# AD9834.net
KiCad netlist of a schematic drawn in Altium Designer
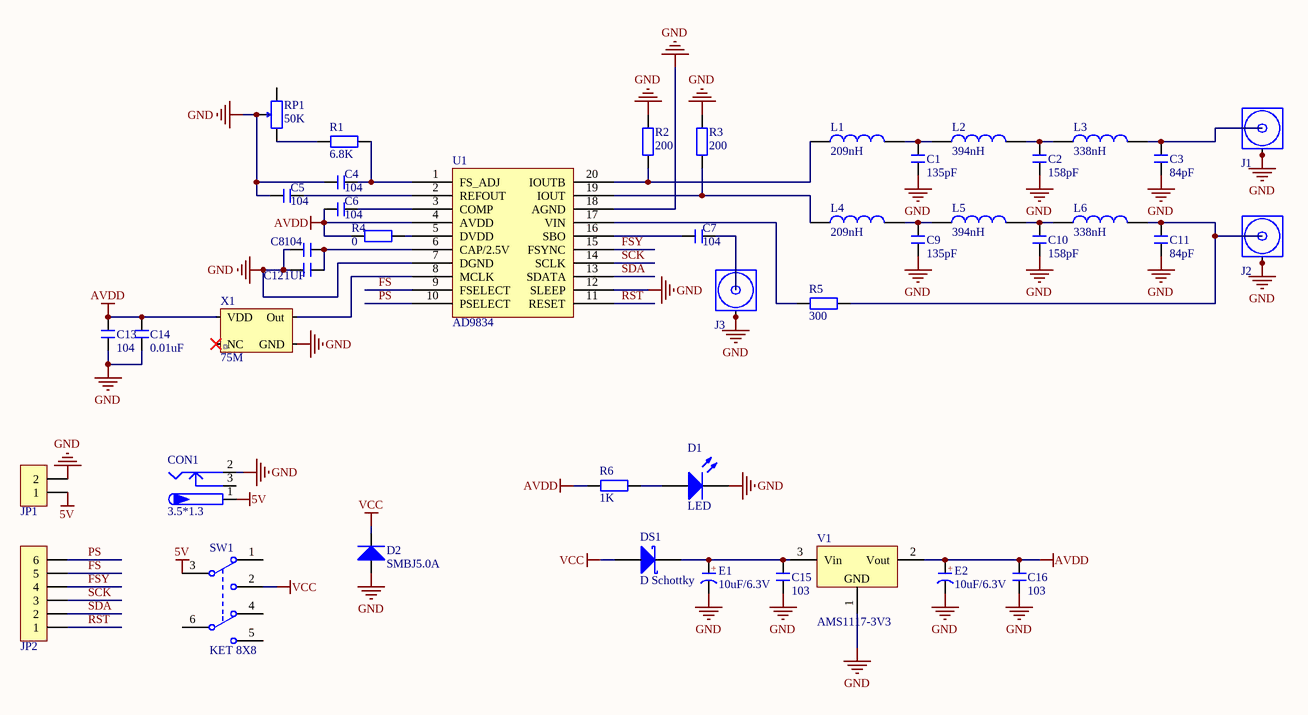
[diagram p0: AD9834.SchDoc]

(export (version "E")
  (design (tool "Eeschema 10.0.6"))
  (components
    (comp (ref "C1")
      (value "135pF")
      (footprint "C 0603")
      (description "无极性贴片电容")
      (fields (field (name "版权归属") "源创客"))
      (libsource (lib "电阻-电容-电感") (part "C"))
    )
    (comp (ref "C2")
      (value "158pF")
      (footprint "C 0603")
      (description "无极性贴片电容")
      (fields (field (name "版权归属") "源创客"))
      (libsource (lib "电阻-电容-电感") (part "C"))
    )
    (comp (ref "C3")
      (value "84pF")
      (footprint "C 0603")
      (description "无极性贴片电容")
      (fields (field (name "版权归属") "源创客"))
      (libsource (lib "电阻-电容-电感") (part "C"))
    )
    (comp (ref "C4")
      (value "104")
      (footprint "C 0805")
      (description "无极性贴片电容")
      (fields (field (name "版权归属") "源创客"))
      (libsource (lib "电阻-电容-电感") (part "C"))
    )
    (comp (ref "C5")
      (value "104")
      (footprint "C 0805")
      (description "无极性贴片电容")
      (fields (field (name "版权归属") "源创客"))
      (libsource (lib "电阻-电容-电感") (part "C"))
    )
    (comp (ref "C6")
      (value "104")
      (footprint "C 0805")
      (description "无极性贴片电容")
      (fields (field (name "版权归属") "源创客"))
      (libsource (lib "电阻-电容-电感") (part "C"))
    )
    (comp (ref "C7")
      (value "104")
      (footprint "C 0805")
      (description "无极性贴片电容")
      (fields (field (name "版权归属") "源创客"))
      (libsource (lib "电阻-电容-电感") (part "C"))
    )
    (comp (ref "C8")
      (value "104")
      (footprint "C 0805")
      (description "无极性贴片电容")
      (fields (field (name "版权归属") "源创客"))
      (libsource (lib "电阻-电容-电感") (part "C"))
    )
    (comp (ref "C9")
      (value "135pF")
      (footprint "C 0603")
      (description "无极性贴片电容")
      (fields (field (name "版权归属") "源创客"))
      (libsource (lib "电阻-电容-电感") (part "C"))
    )
    (comp (ref "C10")
      (value "158pF")
      (footprint "C 0603")
      (description "无极性贴片电容")
      (fields (field (name "版权归属") "源创客"))
      (libsource (lib "电阻-电容-电感") (part "C"))
    )
    (comp (ref "C11")
      (value "84pF")
      (footprint "C 0603")
      (description "无极性贴片电容")
      (fields (field (name "版权归属") "源创客"))
      (libsource (lib "电阻-电容-电感") (part "C"))
    )
    (comp (ref "C12")
      (value "1UF")
      (footprint "C 0805")
      (description "无极性贴片电容")
      (fields (field (name "版权归属") "源创客"))
      (libsource (lib "电阻-电容-电感") (part "C"))
    )
    (comp (ref "C13")
      (value "104")
      (footprint "C 0805")
      (description "无极性贴片电容")
      (fields (field (name "版权归属") "源创客"))
      (libsource (lib "电阻-电容-电感") (part "C"))
    )
    (comp (ref "C14")
      (value "0.01uF")
      (footprint "C 0805")
      (description "无极性贴片电容")
      (fields (field (name "版权归属") "源创客"))
      (libsource (lib "电阻-电容-电感") (part "C"))
    )
    (comp (ref "C15")
      (value "103")
      (footprint "C 0805")
      (description "无极性贴片电容")
      (fields (field (name "版权归属") "源创客"))
      (libsource (lib "电阻-电容-电感") (part "C"))
    )
    (comp (ref "C16")
      (value "103")
      (footprint "C 0805")
      (description "无极性贴片电容")
      (fields (field (name "版权归属") "源创客"))
      (libsource (lib "电阻-电容-电感") (part "C"))
    )
    (comp (ref "CON1")
      (value "3.5*1.3")
      (footprint "DC-005")
      (description "低压电源接口")
      (fields (field (name "版权归属") "源创客"))
      (libsource (lib "接口类") (part "P-DC"))
    )
    (comp (ref "D1")
      (value "LED")
      (footprint "LED_0805")
      (description "发光二极管")
      (fields (field (name "PUBLISHER") "Altium Limited"))
      (libsource (lib "LIB") (part "LED"))
    )
    (comp (ref "D2")
      (value "TVS")
      (footprint "DIODE-SMB")
      (description "TVS保护")
      (fields (field (name "TYPE") "SMBJ5.0A") (field (name "PUBLISHER") "Altium Limited"))
      (libsource (lib "LIB") (part "TVS"))
    )
    (comp (ref "DS1")
      (value "D Schottky")
      (footprint "SMB")
      (description "Schottky Diode")
      (fields (field (name "PUBLISHER") "Altium Limited"))
      (libsource (lib "LIB") (part "D Schottky"))
    )
    (comp (ref "E1")
      (value "10uF/6.3V")
      (footprint "CD B(3528)")
      (description "贴片钽电容")
      (fields (field (name "版权归属") "源创客"))
      (libsource (lib "电阻-电容-电感") (part "C-CD"))
    )
    (comp (ref "E2")
      (value "10uF/6.3V")
      (footprint "CD B(3528)")
      (description "贴片钽电容")
      (fields (field (name "版权归属") "源创客"))
      (libsource (lib "电阻-电容-电感") (part "C-CD"))
    )
    (comp (ref "J1") (value "COAX") (footprint "MCX5.08-5-H") (libsource (lib "LIB") (part "COAX")))
    (comp (ref "J2") (value "COAX") (footprint "MCX5.08-5-H") (libsource (lib "LIB") (part "COAX")))
    (comp (ref "J3") (value "COAX") (footprint "MCX5.08-5-H") (libsource (lib "LIB") (part "COAX")))
    (comp (ref "JP1")
      (value "HDR-1X2")
      (footprint "XH2.54-2P_H")
      (description "2P接插件")
      (fields (field (name "版权归属") "源创客"))
      (libsource (lib "接插件") (part "Header 2"))
    )
    (comp (ref "JP2")
      (value "HDR-1X6")
      (footprint "HDR-1X6")
      (description "6P接插件")
      (fields (field (name "版权归属") "源创客"))
      (libsource (lib "接插件") (part "Header 6"))
    )
    (comp (ref "L1")
      (value "209nH")
      (footprint "L 0603")
      (description "小功率贴片电感")
      (fields (field (name "版权归属") "源创客"))
      (libsource (lib "电阻-电容-电感") (part "L"))
    )
    (comp (ref "L2")
      (value "394nH")
      (footprint "L 0603")
      (description "小功率贴片电感")
      (fields (field (name "版权归属") "源创客"))
      (libsource (lib "电阻-电容-电感") (part "L"))
    )
    (comp (ref "L3")
      (value "338nH")
      (footprint "L 0603")
      (description "小功率贴片电感")
      (fields (field (name "版权归属") "源创客"))
      (libsource (lib "电阻-电容-电感") (part "L"))
    )
    (comp (ref "L4")
      (value "209nH")
      (footprint "L 0603")
      (description "小功率贴片电感")
      (fields (field (name "版权归属") "源创客"))
      (libsource (lib "电阻-电容-电感") (part "L"))
    )
    (comp (ref "L5")
      (value "394nH")
      (footprint "L 0603")
      (description "小功率贴片电感")
      (fields (field (name "版权归属") "源创客"))
      (libsource (lib "电阻-电容-电感") (part "L"))
    )
    (comp (ref "L6")
      (value "338nH")
      (footprint "L 0603")
      (description "小功率贴片电感")
      (fields (field (name "版权归属") "源创客"))
      (libsource (lib "电阻-电容-电感") (part "L"))
    )
    (comp (ref "R1")
      (value "6.8K")
      (footprint "R 0603")
      (description "贴片电阻")
      (fields (field (name "版权归属") "源创客"))
      (libsource (lib "电阻-电容-电感") (part "R"))
    )
    (comp (ref "R2")
      (value "200")
      (footprint "R 0603")
      (description "贴片电阻")
      (fields (field (name "版权归属") "源创客"))
      (libsource (lib "电阻-电容-电感") (part "R"))
    )
    (comp (ref "R3")
      (value "200")
      (footprint "R 0603")
      (description "贴片电阻")
      (fields (field (name "版权归属") "源创客"))
      (libsource (lib "电阻-电容-电感") (part "R"))
    )
    (comp (ref "R4")
      (value "0")
      (footprint "R 0603")
      (description "贴片电阻")
      (fields (field (name "版权归属") "源创客"))
      (libsource (lib "电阻-电容-电感") (part "R"))
    )
    (comp (ref "R5")
      (value "300")
      (footprint "R 0603")
      (description "贴片电阻")
      (fields (field (name "版权归属") "源创客"))
      (libsource (lib "电阻-电容-电感") (part "R"))
    )
    (comp (ref "R6")
      (value "1K")
      (footprint "R 0805")
      (description "贴片电阻")
      (fields (field (name "版权归属") "源创客"))
      (libsource (lib "电阻-电容-电感") (part "R"))
    )
    (comp (ref "RP1")
      (value "50K")
      (footprint "3296W")
      (description "插件单联电位器")
      (fields (field (name "版权归属") "源创客"))
      (libsource (lib "电阻-电容-电感") (part "RP-ID"))
    )
    (comp (ref "SW1")
      (value "KET 8X8")
      (footprint "KFT DIP-8X8")
      (description "8*8自锁开关")
      (fields (field (name "版权归属") "源创客"))
      (libsource (lib "按键-开关") (part "KET 8X8"))
    )
    (comp (ref "U1")
      (value "AD9834")
      (footprint "TSSOP20_N")
      (description "20mW Power,2,3V to 5.5V,75MHz, Complete DDS")
      (libsource (lib "LIB") (part "AD9834"))
    )
    (comp (ref "V1")
      (value "AMS1117-3V3")
      (footprint "SOT223_N")
      (description "三端稳压芯片")
      (fields (field (name "版权归属") "源创客"))
      (libsource (lib "IC芯片") (part "AMS1117"))
    )
    (comp (ref "X1")
      (value "75M")
      (footprint "X-CPX75")
      (description "有源晶振")
      (fields (field (name "FREQUENCY") "75M"))
      (libsource (lib "LIB") (part "XTAL_Oscillator"))
    )
  )
  (nets
    (net (code "1") (name "/FS") (class "Default")
      (node (ref "JP2") (pin "5") (pinfunction "5_5") (pintype "passive"))
      (node (ref "U1") (pin "9") (pinfunction "FSELECT_9") (pintype "passive"))
    )
    (net (code "2") (name "/FSY") (class "Default")
      (node (ref "JP2") (pin "4") (pinfunction "4_4") (pintype "passive"))
      (node (ref "U1") (pin "15") (pinfunction "FSYNC_15") (pintype "passive"))
    )
    (net (code "3") (name "/PS") (class "Default")
      (node (ref "JP2") (pin "6") (pinfunction "6_6") (pintype "passive"))
      (node (ref "U1") (pin "10") (pinfunction "PSELECT_10") (pintype "passive"))
    )
    (net (code "4") (name "/RST") (class "Default")
      (node (ref "JP2") (pin "1") (pinfunction "1_1") (pintype "passive"))
      (node (ref "U1") (pin "11") (pinfunction "RESET_11") (pintype "passive"))
    )
    (net (code "5") (name "/SCK") (class "Default")
      (node (ref "JP2") (pin "3") (pinfunction "3_3") (pintype "passive"))
      (node (ref "U1") (pin "14") (pinfunction "SCLK_14") (pintype "passive"))
    )
    (net (code "6") (name "/SDA") (class "Default")
      (node (ref "JP2") (pin "2") (pinfunction "2_2") (pintype "passive"))
      (node (ref "U1") (pin "13") (pinfunction "SDATA_13") (pintype "passive"))
    )
    (net (code "7") (name "5V") (class "Default")
      (node (ref "CON1") (pin "1") (pintype "power_in"))
      (node (ref "JP1") (pin "1") (pinfunction "1_1") (pintype "passive"))
      (node (ref "SW1") (pin "3") (pinfunction "NO1_3") (pintype "passive"))
    )
    (net (code "8") (name "AVDD") (class "Default")
      (node (ref "C13") (pin "2") (pinfunction "2_2") (pintype "passive"))
      (node (ref "C14") (pin "2") (pinfunction "2_2") (pintype "passive"))
      (node (ref "C16") (pin "2") (pinfunction "2_2") (pintype "passive"))
      (node (ref "C6") (pin "1") (pinfunction "1_1") (pintype "passive"))
      (node (ref "E2") (pin "1") (pinfunction "A_1") (pintype "passive"))
      (node (ref "R4") (pin "1") (pinfunction "1_1") (pintype "passive"))
      (node (ref "R6") (pin "1") (pinfunction "1_1") (pintype "passive"))
      (node (ref "U1") (pin "4") (pinfunction "AVDD_4") (pintype "passive"))
      (node (ref "V1") (pin "2") (pinfunction "Vout_2") (pintype "passive"))
      (node (ref "X1") (pin "4") (pinfunction "VDD_4") (pintype "passive"))
    )
    (net (code "9") (name "GND") (class "Default")
      (node (ref "C1") (pin "1") (pinfunction "1_1") (pintype "passive"))
      (node (ref "C10") (pin "1") (pinfunction "1_1") (pintype "passive"))
      (node (ref "C11") (pin "1") (pinfunction "1_1") (pintype "passive"))
      (node (ref "C12") (pin "1") (pinfunction "1_1") (pintype "passive"))
      (node (ref "C13") (pin "1") (pinfunction "1_1") (pintype "passive"))
      (node (ref "C14") (pin "1") (pinfunction "1_1") (pintype "passive"))
      (node (ref "C15") (pin "1") (pinfunction "1_1") (pintype "passive"))
      (node (ref "C16") (pin "1") (pinfunction "1_1") (pintype "passive"))
      (node (ref "C2") (pin "1") (pinfunction "1_1") (pintype "passive"))
      (node (ref "C3") (pin "1") (pinfunction "1_1") (pintype "passive"))
      (node (ref "C4") (pin "1") (pinfunction "1_1") (pintype "passive"))
      (node (ref "C5") (pin "1") (pinfunction "1_1") (pintype "passive"))
      (node (ref "C8") (pin "1") (pinfunction "1_1") (pintype "passive"))
      (node (ref "C9") (pin "1") (pinfunction "1_1") (pintype "passive"))
      (node (ref "CON1") (pin "2") (pintype "power_in"))
      (node (ref "D1") (pin "2") (pinfunction "K_2") (pintype "passive"))
      (node (ref "D2") (pin "1") (pinfunction "A_1") (pintype "passive"))
      (node (ref "E1") (pin "2") (pinfunction "K_2") (pintype "passive"))
      (node (ref "E2") (pin "2") (pinfunction "K_2") (pintype "passive"))
      (node (ref "J1") (pin "2") (pinfunction "GND_2") (pintype "passive"))
      (node (ref "J1") (pin "3") (pinfunction "GND_3") (pintype "passive"))
      (node (ref "J1") (pin "4") (pinfunction "GND_4") (pintype "passive"))
      (node (ref "J1") (pin "5") (pinfunction "GND_5") (pintype "passive"))
      (node (ref "J2") (pin "2") (pinfunction "GND_2") (pintype "passive"))
      (node (ref "J2") (pin "3") (pinfunction "GND_3") (pintype "passive"))
      (node (ref "J2") (pin "4") (pinfunction "GND_4") (pintype "passive"))
      (node (ref "J2") (pin "5") (pinfunction "GND_5") (pintype "passive"))
      (node (ref "J3") (pin "2") (pinfunction "GND_2") (pintype "passive"))
      (node (ref "J3") (pin "3") (pinfunction "GND_3") (pintype "passive"))
      (node (ref "J3") (pin "4") (pinfunction "GND_4") (pintype "passive"))
      (node (ref "J3") (pin "5") (pinfunction "GND_5") (pintype "passive"))
      (node (ref "JP1") (pin "2") (pinfunction "2_2") (pintype "passive"))
      (node (ref "R2") (pin "1") (pinfunction "1_1") (pintype "passive"))
      (node (ref "R3") (pin "1") (pinfunction "1_1") (pintype "passive"))
      (node (ref "RP1") (pin "2") (pinfunction "2_2") (pintype "passive"))
      (node (ref "U1") (pin "12") (pinfunction "SLEEP_12") (pintype "passive"))
      (node (ref "U1") (pin "18") (pinfunction "AGND_18") (pintype "passive"))
      (node (ref "U1") (pin "7") (pinfunction "DGND_7") (pintype "passive"))
      (node (ref "V1") (pin "1") (pinfunction "GND_1") (pintype "passive"))
      (node (ref "X1") (pin "2") (pinfunction "GND_2") (pintype "passive"))
    )
    (net (code "10") (name "Net-(C1-Pad2)") (class "Default")
      (node (ref "C1") (pin "2") (pinfunction "2_2") (pintype "passive"))
      (node (ref "L1") (pin "2") (pinfunction "2_2") (pintype "passive"))
      (node (ref "L2") (pin "1") (pinfunction "1_1") (pintype "passive"))
    )
    (net (code "11") (name "Net-(C2-Pad2)") (class "Default")
      (node (ref "C2") (pin "2") (pinfunction "2_2") (pintype "passive"))
      (node (ref "L2") (pin "2") (pinfunction "2_2") (pintype "passive"))
      (node (ref "L3") (pin "1") (pinfunction "1_1") (pintype "passive"))
    )
    (net (code "12") (name "Net-(C9-Pad2)") (class "Default")
      (node (ref "C9") (pin "2") (pinfunction "2_2") (pintype "passive"))
      (node (ref "L4") (pin "2") (pinfunction "2_2") (pintype "passive"))
      (node (ref "L5") (pin "1") (pinfunction "1_1") (pintype "passive"))
    )
    (net (code "13") (name "Net-(C10-Pad2)") (class "Default")
      (node (ref "C10") (pin "2") (pinfunction "2_2") (pintype "passive"))
      (node (ref "L5") (pin "2") (pinfunction "2_2") (pintype "passive"))
      (node (ref "L6") (pin "1") (pinfunction "1_1") (pintype "passive"))
    )
    (net (code "14") (name "Net-(D1-A)") (class "Default")
      (node (ref "D1") (pin "1") (pinfunction "A_1") (pintype "passive"))
      (node (ref "R6") (pin "2") (pinfunction "2_2") (pintype "passive"))
    )
    (net (code "15") (name "Net-(E1-A)") (class "Default")
      (node (ref "C15") (pin "2") (pinfunction "2_2") (pintype "passive"))
      (node (ref "DS1") (pin "2") (pinfunction "2_2") (pintype "passive"))
      (node (ref "E1") (pin "1") (pinfunction "A_1") (pintype "passive"))
      (node (ref "V1") (pin "3") (pinfunction "Vin_3") (pintype "passive"))
    )
    (net (code "16") (name "Net-(J1-Signal)") (class "Default")
      (node (ref "C3") (pin "2") (pinfunction "2_2") (pintype "passive"))
      (node (ref "J1") (pin "1") (pinfunction "Signal_1") (pintype "passive"))
      (node (ref "L3") (pin "2") (pinfunction "2_2") (pintype "passive"))
    )
    (net (code "17") (name "Net-(J2-Signal)") (class "Default")
      (node (ref "C11") (pin "2") (pinfunction "2_2") (pintype "passive"))
      (node (ref "J2") (pin "1") (pinfunction "Signal_1") (pintype "passive"))
      (node (ref "L6") (pin "2") (pinfunction "2_2") (pintype "passive"))
      (node (ref "R5") (pin "2") (pinfunction "2_2") (pintype "passive"))
    )
    (net (code "18") (name "Net-(J3-Signal)") (class "Default")
      (node (ref "C7") (pin "2") (pinfunction "2_2") (pintype "passive"))
      (node (ref "J3") (pin "1") (pinfunction "Signal_1") (pintype "passive"))
    )
    (net (code "19") (name "Net-(R1-Pad1)") (class "Default")
      (node (ref "R1") (pin "1") (pinfunction "1_1") (pintype "passive"))
      (node (ref "RP1") (pin "1") (pinfunction "1_1") (pintype "passive"))
    )
    (net (code "20") (name "Net-(U1-CAP{slash}2.5V)") (class "Default")
      (node (ref "C12") (pin "2") (pinfunction "2_2") (pintype "passive"))
      (node (ref "C8") (pin "2") (pinfunction "2_2") (pintype "passive"))
      (node (ref "U1") (pin "6") (pinfunction "CAP/2.5V_6") (pintype "passive"))
    )
    (net (code "21") (name "Net-(U1-COMP)") (class "Default")
      (node (ref "C6") (pin "2") (pinfunction "2_2") (pintype "passive"))
      (node (ref "U1") (pin "3") (pinfunction "COMP_3") (pintype "passive"))
    )
    (net (code "22") (name "Net-(U1-DVDD)") (class "Default")
      (node (ref "R4") (pin "2") (pinfunction "2_2") (pintype "passive"))
      (node (ref "U1") (pin "5") (pinfunction "DVDD_5") (pintype "passive"))
    )
    (net (code "23") (name "Net-(U1-FS_ADJ)") (class "Default")
      (node (ref "C4") (pin "2") (pinfunction "2_2") (pintype "passive"))
      (node (ref "R1") (pin "2") (pinfunction "2_2") (pintype "passive"))
      (node (ref "U1") (pin "1") (pinfunction "FS_ADJ_1") (pintype "passive"))
    )
    (net (code "24") (name "Net-(U1-IOUT)") (class "Default")
      (node (ref "L4") (pin "1") (pinfunction "1_1") (pintype "passive"))
      (node (ref "R3") (pin "2") (pinfunction "2_2") (pintype "passive"))
      (node (ref "U1") (pin "19") (pinfunction "IOUT_19") (pintype "passive"))
    )
    (net (code "25") (name "Net-(U1-IOUTB)") (class "Default")
      (node (ref "L1") (pin "1") (pinfunction "1_1") (pintype "passive"))
      (node (ref "R2") (pin "2") (pinfunction "2_2") (pintype "passive"))
      (node (ref "U1") (pin "20") (pinfunction "IOUTB_20") (pintype "passive"))
    )
    (net (code "26") (name "Net-(U1-MCLK)") (class "Default")
      (node (ref "U1") (pin "8") (pinfunction "MCLK_8") (pintype "passive"))
      (node (ref "X1") (pin "3") (pinfunction "Out_3") (pintype "passive"))
    )
    (net (code "27") (name "Net-(U1-REFOUT)") (class "Default")
      (node (ref "C5") (pin "2") (pinfunction "2_2") (pintype "passive"))
      (node (ref "U1") (pin "2") (pinfunction "REFOUT_2") (pintype "passive"))
    )
    (net (code "28") (name "Net-(U1-SBO)") (class "Default")
      (node (ref "C7") (pin "1") (pinfunction "1_1") (pintype "passive"))
      (node (ref "U1") (pin "16") (pinfunction "SBO_16") (pintype "passive"))
    )
    (net (code "29") (name "Net-(U1-VIN)") (class "Default")
      (node (ref "R5") (pin "1") (pinfunction "1_1") (pintype "passive"))
      (node (ref "U1") (pin "17") (pinfunction "VIN_17") (pintype "passive"))
    )
    (net (code "30") (name "VCC") (class "Default")
      (node (ref "D2") (pin "2") (pinfunction "K_2") (pintype "passive"))
      (node (ref "DS1") (pin "1") (pinfunction "1_1") (pintype "passive"))
      (node (ref "SW1") (pin "2") (pinfunction "COM2_2") (pintype "passive"))
    )
    (net (code "31") (name "unconnected-(CON1-Pad3)") (class "Default")
      (node (ref "CON1") (pin "3") (pintype "power_in"))
    )
    (net (code "32") (name "unconnected-(RP1-Pad3)") (class "Default")
      (node (ref "RP1") (pin "3") (pinfunction "3_3") (pintype "passive"))
    )
    (net (code "33") (name "unconnected-(SW1-COM2-Pad5)") (class "Default")
      (node (ref "SW1") (pin "5") (pinfunction "COM2_5") (pintype "passive"))
    )
    (net (code "34") (name "unconnected-(SW1-NC1-Pad1)") (class "Default")
      (node (ref "SW1") (pin "1") (pinfunction "NC1_1") (pintype "passive"))
    )
    (net (code "35") (name "unconnected-(SW1-NC2-Pad6)") (class "Default")
      (node (ref "SW1") (pin "6") (pinfunction "NC2_6") (pintype "passive"))
    )
    (net (code "36") (name "unconnected-(SW1-NO2-Pad4)") (class "Default")
      (node (ref "SW1") (pin "4") (pinfunction "NO2_4") (pintype "passive"))
    )
    (net (code "37") (name "unconnected-(X1-NC-Pad1)") (class "Default")
      (node (ref "X1") (pin "1") (pinfunction "NC_1") (pintype "passive+no_connect"))
    )
  )
)
